# Input_Filter.net
KiCad netlist of a schematic drawn in Altium Designer
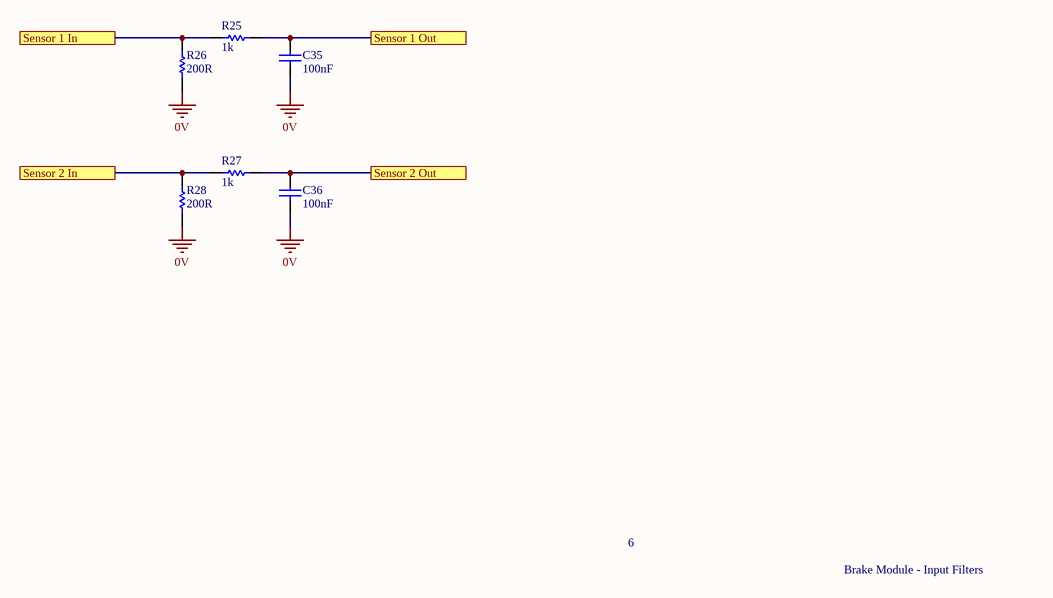
[diagram p0: Input Filter.SchDoc]

(export (version "E")
  (design (tool "Eeschema 10.0.6"))
  (components
    (comp (ref "C35")
      (value "100nF")
      (footprint "0805")
      (fields
        (field (name "PART NUMBER") "GCM21BR71H104KA37L")
        (field (name "TOLERANCE") "±10%")
        (field (name "MANUFACTURER") "muRata")
      )
      (libsource (lib "ts_20-standard-library") (part "Capacitor"))
    )
    (comp (ref "C36")
      (value "100nF")
      (footprint "0805")
      (fields
        (field (name "PART NUMBER") "GCM21BR71H104KA37L")
        (field (name "TOLERANCE") "±10%")
        (field (name "MANUFACTURER") "muRata")
      )
      (libsource (lib "ts_20-standard-library") (part "Capacitor"))
    )
    (comp (ref "R25")
      (value "1k")
      (footprint "0805")
      (fields
        (field (name "PART NUMBER") "RC0805FR071KL")
        (field (name "MANUFACTURER") "YAGEO")
        (field (name "TOLERANCE") "0.01")
      )
      (libsource (lib "ts_20-standard-library") (part "Resistor"))
    )
    (comp (ref "R26")
      (value "200R")
      (footprint "0805")
      (fields
        (field (name "PART NUMBER") "RC0805FR07200RL")
        (field (name "MANUFACTURER") "YAGEO")
        (field (name "TOLERANCE") "0.01")
      )
      (libsource (lib "ts_20-standard-library") (part "Resistor"))
    )
    (comp (ref "R27")
      (value "1k")
      (footprint "0805")
      (fields
        (field (name "PART NUMBER") "RC0805FR071KL")
        (field (name "MANUFACTURER") "YAGEO")
        (field (name "TOLERANCE") "0.01")
      )
      (libsource (lib "ts_20-standard-library") (part "Resistor"))
    )
    (comp (ref "R28")
      (value "200R")
      (footprint "0805")
      (fields
        (field (name "PART NUMBER") "RC0805FR07200RL")
        (field (name "MANUFACTURER") "YAGEO")
        (field (name "TOLERANCE") "0.01")
      )
      (libsource (lib "ts_20-standard-library") (part "Resistor"))
    )
  )
  (nets
    (net (code "1") (name "/Sensor 1 In") (class "Default")
      (node (ref "R25") (pin "1") (pinfunction "1_1") (pintype "passive"))
      (node (ref "R26") (pin "2") (pinfunction "2_2") (pintype "passive"))
    )
    (net (code "2") (name "/Sensor 1 Out") (class "Default")
      (node (ref "C35") (pin "2") (pinfunction "2_2") (pintype "passive"))
      (node (ref "R25") (pin "2") (pinfunction "2_2") (pintype "passive"))
    )
    (net (code "3") (name "/Sensor 2 In") (class "Default")
      (node (ref "R27") (pin "1") (pinfunction "1_1") (pintype "passive"))
      (node (ref "R28") (pin "2") (pinfunction "2_2") (pintype "passive"))
    )
    (net (code "4") (name "/Sensor 2 Out") (class "Default")
      (node (ref "C36") (pin "2") (pinfunction "2_2") (pintype "passive"))
      (node (ref "R27") (pin "2") (pinfunction "2_2") (pintype "passive"))
    )
    (net (code "5") (name "0V") (class "Default")
      (node (ref "C35") (pin "1") (pinfunction "1_1") (pintype "passive"))
      (node (ref "C36") (pin "1") (pinfunction "1_1") (pintype "passive"))
      (node (ref "R26") (pin "1") (pinfunction "1_1") (pintype "passive"))
      (node (ref "R28") (pin "1") (pinfunction "1_1") (pintype "passive"))
    )
  )
)
